# TSL2591.net
KiCad netlist of a schematic drawn in Altium Designer
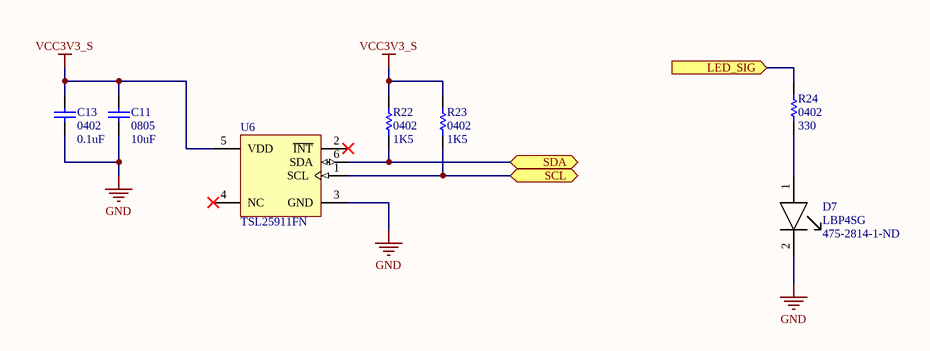
[diagram p0: TSL2591.SchDoc]

(export (version "E")
  (design (tool "Eeschema 10.0.6"))
  (components
    (comp (ref "C11")
      (value "0805")
      (footprint "CAP0805R")
      (description "Capacitor")
      (fields
        (field (name "ALTIUM_VALUE") "10uF")
        (field (name "MANUFACTURER") "TDK")
        (field (name "MANUFACTURER PART NUMBER") "CGA4J1X7R0J106K125AC")
        (field (name "PUBLISHER") "Altium Limited")
      )
      (libsource (lib "Miscellaneous Devices") (part "Cap"))
    )
    (comp (ref "C13")
      (value "0402")
      (footprint "CAP0402R")
      (description "Capacitor")
      (fields
        (field (name "ALTIUM_VALUE") "0.1uF")
        (field (name "MANUFACTURER") "Murata")
        (field (name "MANUFACTURER PART NUMBER") "GCM155R71C104KA55J")
        (field (name "PUBLISHER") "Altium Limited")
      )
      (libsource (lib "Miscellaneous Devices") (part "Cap"))
    )
    (comp (ref "D7")
      (value "LBP4SG")
      (footprint "LB P4SG")
      (description "LED BLUE CLEAR SMD BOTTOM ENTRY")
      (fields (field (name "SUPPLIER PART NUMBER 1") "475-2814-1-ND"))
      (libsource (lib "PAY") (part "LB P4SG"))
    )
    (comp (ref "R22")
      (value "0402")
      (footprint "RES0402R")
      (description "Resistor")
      (fields (field (name "ALTIUM_VALUE") "1K5") (field (name "PUBLISHER") "Altium Limited"))
      (libsource (lib "Miscellaneous Devices") (part "Res1"))
    )
    (comp (ref "R23")
      (value "0402")
      (footprint "RES0402R")
      (description "Resistor")
      (fields (field (name "ALTIUM_VALUE") "1K5") (field (name "PUBLISHER") "Altium Limited"))
      (libsource (lib "Miscellaneous Devices") (part "Res1"))
    )
    (comp (ref "R24")
      (value "0402")
      (footprint "RES0402R")
      (description "Resistor")
      (fields (field (name "ALTIUM_VALUE") "330") (field (name "PUBLISHER") "Altium Limited"))
      (libsource (lib "Miscellaneous Devices") (part "Res1"))
    )
    (comp (ref "U6")
      (value "TSL25911FN")
      (footprint "AMS-FN-6-2400X2000DE_V")
      (description "Light-to-Digital Converter with I2C Interface, 2.7 to 3.6 V, -30 to 70 degC, FN-6, Pb-Free, Reel")
      (fields (field (name "MANUFACTURER") "AMS"))
      (libsource (lib "PAY") (part "TSL25911FN"))
    )
  )
  (nets
    (net (code "1") (name "/LED_SIG") (class "Default")
      (node (ref "R24") (pin "1") (pinfunction "1_1") (pintype "passive"))
    )
    (net (code "2") (name "/SCL") (class "Default")
      (node (ref "R23") (pin "1") (pinfunction "1_1") (pintype "passive"))
      (node (ref "U6") (pin "1") (pinfunction "SCL_1") (pintype "input"))
    )
    (net (code "3") (name "/SDA") (class "Default")
      (node (ref "R22") (pin "1") (pinfunction "1_1") (pintype "passive"))
      (node (ref "U6") (pin "6") (pinfunction "SDA_6") (pintype "bidirectional"))
    )
    (net (code "4") (name "GND") (class "Default")
      (node (ref "C11") (pin "1") (pinfunction "1_1") (pintype "passive"))
      (node (ref "C13") (pin "1") (pinfunction "1_1") (pintype "passive"))
      (node (ref "D7") (pin "2") (pinfunction "Cathode_2") (pintype "passive"))
      (node (ref "U6") (pin "3") (pinfunction "GND_3") (pintype "power_in"))
    )
    (net (code "5") (name "Net-(D7-Anode)") (class "Default")
      (node (ref "D7") (pin "1") (pinfunction "Anode_1") (pintype "passive"))
      (node (ref "R24") (pin "2") (pinfunction "2_2") (pintype "passive"))
    )
    (net (code "6") (name "VCC3V3_S") (class "Default")
      (node (ref "C11") (pin "2") (pinfunction "2_2") (pintype "passive"))
      (node (ref "C13") (pin "2") (pinfunction "2_2") (pintype "passive"))
      (node (ref "R22") (pin "2") (pinfunction "2_2") (pintype "passive"))
      (node (ref "R23") (pin "2") (pinfunction "2_2") (pintype "passive"))
      (node (ref "U6") (pin "5") (pinfunction "VDD_5") (pintype "power_in"))
    )
    (net (code "7") (name "unconnected-(U6-NC-Pad4)") (class "Default")
      (node (ref "U6") (pin "4") (pinfunction "NC_4") (pintype "passive+no_connect"))
    )
    (net (code "8") (name "unconnected-(U6-~{INT}-Pad2)") (class "Default")
      (node (ref "U6") (pin "2") (pinfunction "~{INT}_2") (pintype "open_collector+no_connect"))
    )
  )
)
